# hunger_cube.net
KiCad netlist of a schematic drawn in EAGLE
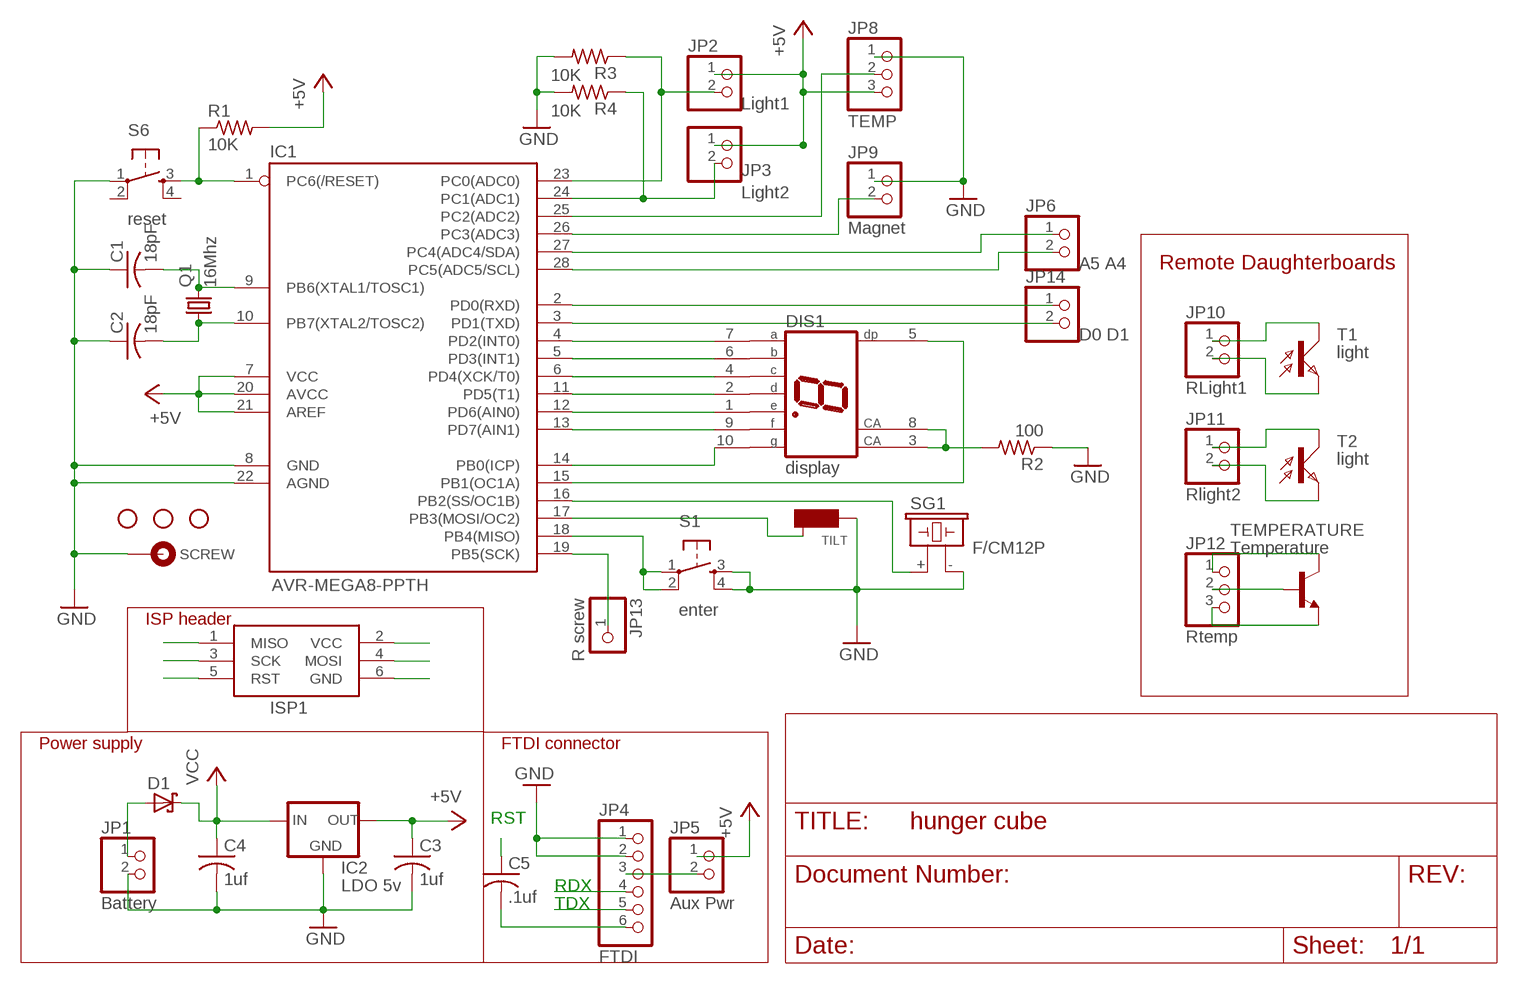
[diagram p0: schematic, sheet 1]

(export (version "E")
  (design (tool "Eeschema 10.0.6"))
  (components
    (comp (ref "C1")
      (value "18pF")
      (footprint "eagle-import:C025-050X050")
      (libsource (lib "eagle-import") (part "C-US025-050X050"))
    )
    (comp (ref "C2")
      (value "18pF")
      (footprint "eagle-import:C025-050X050")
      (libsource (lib "eagle-import") (part "C-US025-050X050"))
    )
    (comp (ref "C3")
      (value "1uf")
      (footprint "eagle-import:C025-050X050")
      (libsource (lib "eagle-import") (part "C-US025-050X050"))
    )
    (comp (ref "C4")
      (value "1uf")
      (footprint "eagle-import:C025-050X050")
      (libsource (lib "eagle-import") (part "C-US025-050X050"))
    )
    (comp (ref "C5")
      (value ".1uf")
      (footprint "eagle-import:C025-050X050")
      (libsource (lib "eagle-import") (part "C-US025-050X050"))
    )
    (comp (ref "D1")
      (value "SCHOTTKY-DIODEDO41")
      (footprint "eagle-import:DO41-10")
      (libsource (lib "eagle-import") (part "SCHOTTKY-DIODEDO41"))
    )
    (comp (ref "DIS1")
      (value "display")
      (footprint "eagle-import:HDSP-M")
      (libsource (lib "eagle-import") (part "HD-H101"))
    )
    (comp (ref "IC1")
      (value "AVR-MEGA8-PPTH")
      (footprint "eagle-import:DIL28-3")
      (libsource (lib "eagle-import") (part "AVR-MEGA8-PPTH"))
    )
    (comp (ref "IC2")
      (value "LDO 5v")
      (footprint "eagle-import:TO92-INLINE")
      (libsource (lib "eagle-import") (part "MCP1700INLINE"))
    )
    (comp (ref "ISP1")
      (value "AVRISP-6")
      (footprint "eagle-import:AVRISP")
      (libsource (lib "eagle-import") (part "AVRISP-6"))
    )
    (comp (ref "JP1")
      (value "Battery")
      (footprint "eagle-import:1X02")
      (libsource (lib "eagle-import") (part "PINHD-1X2"))
    )
    (comp (ref "JP2")
      (value "Light1")
      (footprint "eagle-import:1X02")
      (libsource (lib "eagle-import") (part "PINHD-1X2"))
    )
    (comp (ref "JP3")
      (value "Light2")
      (footprint "eagle-import:1X02")
      (libsource (lib "eagle-import") (part "PINHD-1X2"))
    )
    (comp (ref "JP4")
      (value "FTDI")
      (footprint "eagle-import:1X06")
      (libsource (lib "eagle-import") (part "PINHD-1X6"))
    )
    (comp (ref "JP5")
      (value "Aux Pwr")
      (footprint "eagle-import:1X02")
      (libsource (lib "eagle-import") (part "PINHD-1X2"))
    )
    (comp (ref "JP6")
      (value "A5 A4")
      (footprint "eagle-import:1X02")
      (libsource (lib "eagle-import") (part "PINHD-1X2"))
    )
    (comp (ref "JP7")
      (value "Connected screw hole")
      (footprint "eagle-import:SCREW-HOLE-PAD")
      (libsource (lib "eagle-import") (part "CONNECTED-SCREW-HOLE"))
    )
    (comp (ref "JP8")
      (value "TEMP")
      (footprint "eagle-import:1X03")
      (libsource (lib "eagle-import") (part "PINHD-1X3"))
    )
    (comp (ref "JP9")
      (value "Magnet")
      (footprint "eagle-import:1X02")
      (libsource (lib "eagle-import") (part "PINHD-1X2"))
    )
    (comp (ref "JP10")
      (value "RLight1")
      (footprint "eagle-import:1X02")
      (libsource (lib "eagle-import") (part "PINHD-1X2"))
    )
    (comp (ref "JP11")
      (value "Rlight2")
      (footprint "eagle-import:1X02")
      (libsource (lib "eagle-import") (part "PINHD-1X2"))
    )
    (comp (ref "JP12")
      (value "Rtemp")
      (footprint "eagle-import:1X03")
      (libsource (lib "eagle-import") (part "PINHD-1X3"))
    )
    (comp (ref "JP13")
      (value "R screw")
      (footprint "eagle-import:1X01")
      (libsource (lib "eagle-import") (part "PINHD-1X1"))
    )
    (comp (ref "JP14")
      (value "D0 D1")
      (footprint "eagle-import:1X02")
      (libsource (lib "eagle-import") (part "PINHD-1X2"))
    )
    (comp (ref "Q1")
      (value "16Mhz")
      (footprint "eagle-import:HC49US")
      (libsource (lib "eagle-import") (part "CRYSTALHC49US"))
    )
    (comp (ref "R1")
      (value "10K")
      (footprint "eagle-import:0207_12")
      (libsource (lib "eagle-import") (part "R-US_0207/12"))
    )
    (comp (ref "R2")
      (value "100")
      (footprint "eagle-import:0207_12")
      (libsource (lib "eagle-import") (part "R-US_0207/12"))
    )
    (comp (ref "R3")
      (value "10K")
      (footprint "eagle-import:0207_12")
      (libsource (lib "eagle-import") (part "R-US_0207/12"))
    )
    (comp (ref "R4")
      (value "10K")
      (footprint "eagle-import:0207_12")
      (libsource (lib "eagle-import") (part "R-US_0207/12"))
    )
    (comp (ref "S1")
      (value "enter")
      (footprint "eagle-import:TACTILE-PTH")
      (libsource (lib "eagle-import") (part "TAC_SWITCHPTH"))
    )
    (comp (ref "S6")
      (value "reset")
      (footprint "eagle-import:TACTILE-PTH")
      (libsource (lib "eagle-import") (part "TAC_SWITCHPTH"))
    )
    (comp (ref "SG1")
      (value "F/CM12P")
      (footprint "eagle-import:F_CM12P")
      (libsource (lib "eagle-import") (part "F/CM12P"))
    )
    (comp (ref "ST1")
      (value "STAND-OFF")
      (footprint "eagle-import:STAND-OFF")
      (libsource (lib "eagle-import") (part "STAND-OFF"))
    )
    (comp (ref "ST2")
      (value "STAND-OFF")
      (footprint "eagle-import:STAND-OFF")
      (libsource (lib "eagle-import") (part "STAND-OFF"))
    )
    (comp (ref "ST3")
      (value "STAND-OFF")
      (footprint "eagle-import:STAND-OFF")
      (libsource (lib "eagle-import") (part "STAND-OFF"))
    )
    (comp (ref "T1")
      (value "light")
      (footprint "eagle-import:BPX81")
      (libsource (lib "eagle-import") (part "BPX81"))
    )
    (comp (ref "T2")
      (value "light")
      (footprint "eagle-import:BPX81")
      (libsource (lib "eagle-import") (part "BPX81"))
    )
    (comp (ref "TEMPERATURE")
      (value "Temperature")
      (footprint "eagle-import:TO92-EBC")
      (libsource (lib "eagle-import") (part "-NPN-TO92-EBC"))
    )
    (comp (ref "TILT")
      (value "TILT-SENSOR")
      (footprint "eagle-import:TILT")
      (libsource (lib "eagle-import") (part "TILT-SENSOR"))
    )
  )
  (nets
    (net (code "1") (name "+5V") (class "Default")
      (node (ref "C3") (pin "1") (pinfunction "1_1") (pintype "passive"))
      (node (ref "IC1") (pin "20") (pinfunction "AVCC_20") (pintype "bidirectional"))
      (node (ref "IC1") (pin "21") (pinfunction "AREF_21") (pintype "bidirectional"))
      (node (ref "IC1") (pin "7") (pinfunction "VCC_7") (pintype "bidirectional"))
      (node (ref "IC2") (pin "3") (pinfunction "OUT_3") (pintype "passive"))
      (node (ref "ISP1") (pin "2") (pinfunction "VCC_2") (pintype "power_in"))
      (node (ref "JP2") (pin "1") (pinfunction "1_1") (pintype "passive"))
      (node (ref "JP3") (pin "1") (pinfunction "1_1") (pintype "passive"))
      (node (ref "JP5") (pin "1") (pinfunction "1_1") (pintype "passive"))
      (node (ref "JP8") (pin "3") (pinfunction "3_3") (pintype "passive"))
      (node (ref "R1") (pin "2") (pinfunction "2_2") (pintype "passive"))
    )
    (net (code "2") (name "/D0-RDX") (class "Default")
      (node (ref "IC1") (pin "2") (pinfunction "PD0(RXD)_2") (pintype "bidirectional"))
      (node (ref "JP14") (pin "1") (pinfunction "1_1") (pintype "passive"))
      (node (ref "JP4") (pin "4") (pinfunction "4_4") (pintype "passive"))
    )
    (net (code "3") (name "/D1-TDX") (class "Default")
      (node (ref "IC1") (pin "3") (pinfunction "PD1(TXD)_3") (pintype "bidirectional"))
      (node (ref "JP14") (pin "2") (pinfunction "2_2") (pintype "passive"))
      (node (ref "JP4") (pin "5") (pinfunction "5_5") (pintype "passive"))
    )
    (net (code "4") (name "/D11-MOSI-TILT") (class "Default")
      (node (ref "IC1") (pin "17") (pinfunction "PB3(MOSI/OC2)_17") (pintype "bidirectional"))
      (node (ref "ISP1") (pin "4") (pinfunction "MOSI_4") (pintype "output"))
      (node (ref "TILT") (pin "SLEEVE") (pinfunction "SLEEVE_SLEEVE") (pintype "bidirectional"))
    )
    (net (code "5") (name "/D12-MISO-ENTER") (class "Default")
      (node (ref "IC1") (pin "18") (pinfunction "PB4(MISO)_18") (pintype "bidirectional"))
      (node (ref "ISP1") (pin "1") (pinfunction "MISO_1") (pintype "input"))
      (node (ref "S1") (pin "1") (pinfunction "1_1") (pintype "passive"))
      (node (ref "S1") (pin "2") (pinfunction "2_2") (pintype "passive"))
    )
    (net (code "6") (name "/D13-SCK-SCREW") (class "Default")
      (node (ref "IC1") (pin "19") (pinfunction "PB5(SCK)_19") (pintype "bidirectional"))
      (node (ref "ISP1") (pin "3") (pinfunction "SCK_3") (pintype "output"))
      (node (ref "JP13") (pin "1") (pinfunction "1_1") (pintype "passive"))
    )
    (net (code "7") (name "/RST") (class "Default")
      (node (ref "C5") (pin "1") (pinfunction "1_1") (pintype "passive"))
      (node (ref "IC1") (pin "1") (pinfunction "PC6(/RESET)_1") (pintype "bidirectional"))
      (node (ref "ISP1") (pin "5") (pinfunction "RST_5") (pintype "output"))
      (node (ref "R1") (pin "1") (pinfunction "1_1") (pintype "passive"))
      (node (ref "S6") (pin "3") (pinfunction "3_3") (pintype "passive"))
    )
    (net (code "8") (name "GND") (class "Default")
      (node (ref "C1") (pin "1") (pinfunction "1_1") (pintype "passive"))
      (node (ref "C2") (pin "1") (pinfunction "1_1") (pintype "passive"))
      (node (ref "C3") (pin "2") (pinfunction "2_2") (pintype "passive"))
      (node (ref "C4") (pin "2") (pinfunction "2_2") (pintype "passive"))
      (node (ref "IC1") (pin "22") (pinfunction "AGND_22") (pintype "bidirectional"))
      (node (ref "IC1") (pin "8") (pinfunction "GND_8") (pintype "bidirectional"))
      (node (ref "IC2") (pin "1") (pinfunction "GND_1") (pintype "input"))
      (node (ref "ISP1") (pin "6") (pinfunction "GND_6") (pintype "power_in"))
      (node (ref "JP1") (pin "2") (pinfunction "2_2") (pintype "passive"))
      (node (ref "JP4") (pin "1") (pinfunction "1_1") (pintype "passive"))
      (node (ref "JP4") (pin "2") (pinfunction "2_2") (pintype "passive"))
      (node (ref "JP7") (pin "SCREW") (pinfunction "SCREW_SCREW") (pintype "bidirectional"))
      (node (ref "JP8") (pin "1") (pinfunction "1_1") (pintype "passive"))
      (node (ref "JP9") (pin "1") (pinfunction "1_1") (pintype "passive"))
      (node (ref "R2") (pin "1") (pinfunction "1_1") (pintype "passive"))
      (node (ref "R3") (pin "2") (pinfunction "2_2") (pintype "passive"))
      (node (ref "R4") (pin "2") (pinfunction "2_2") (pintype "passive"))
      (node (ref "S1") (pin "3") (pinfunction "3_3") (pintype "passive"))
      (node (ref "S1") (pin "4") (pinfunction "4_4") (pintype "passive"))
      (node (ref "S6") (pin "1") (pinfunction "1_1") (pintype "passive"))
      (node (ref "SG1") (pin "-") (pinfunction "2_-") (pintype "passive"))
      (node (ref "TILT") (pin "CENTER") (pinfunction "CENTER_CENTER") (pintype "bidirectional"))
    )
    (net (code "9") (name "Net-(C5-Pad2)") (class "Default")
      (node (ref "C5") (pin "2") (pinfunction "2_2") (pintype "passive"))
      (node (ref "JP4") (pin "6") (pinfunction "6_6") (pintype "passive"))
    )
    (net (code "10") (name "Net-(D1-PadA)") (class "Default")
      (node (ref "D1") (pin "A") (pinfunction "A_A") (pintype "passive"))
      (node (ref "JP1") (pin "1") (pinfunction "1_1") (pintype "passive"))
    )
    (net (code "11") (name "Net-(DIS1-A)") (class "Default")
      (node (ref "DIS1") (pin "7") (pinfunction "A_7") (pintype "passive"))
      (node (ref "IC1") (pin "4") (pinfunction "PD2(INT0)_4") (pintype "bidirectional"))
    )
    (net (code "12") (name "Net-(DIS1-B)") (class "Default")
      (node (ref "DIS1") (pin "6") (pinfunction "B_6") (pintype "passive"))
      (node (ref "IC1") (pin "5") (pinfunction "PD3(INT1)_5") (pintype "bidirectional"))
    )
    (net (code "13") (name "Net-(DIS1-C)") (class "Default")
      (node (ref "DIS1") (pin "4") (pinfunction "C_4") (pintype "passive"))
      (node (ref "IC1") (pin "6") (pinfunction "PD4(XCK/T0)_6") (pintype "bidirectional"))
    )
    (net (code "14") (name "Net-(DIS1-CA-Pad3)") (class "Default")
      (node (ref "DIS1") (pin "3") (pinfunction "CA_3") (pintype "passive"))
      (node (ref "DIS1") (pin "8") (pinfunction "CA_8") (pintype "passive"))
      (node (ref "R2") (pin "2") (pinfunction "2_2") (pintype "passive"))
    )
    (net (code "15") (name "Net-(DIS1-D)") (class "Default")
      (node (ref "DIS1") (pin "2") (pinfunction "D_2") (pintype "passive"))
      (node (ref "IC1") (pin "11") (pinfunction "PD5(T1)_11") (pintype "bidirectional"))
    )
    (net (code "16") (name "Net-(DIS1-DP)") (class "Default")
      (node (ref "DIS1") (pin "5") (pinfunction "DP_5") (pintype "passive"))
      (node (ref "IC1") (pin "15") (pinfunction "PB1(OC1A)_15") (pintype "bidirectional"))
    )
    (net (code "17") (name "Net-(DIS1-E)") (class "Default")
      (node (ref "DIS1") (pin "1") (pinfunction "E_1") (pintype "passive"))
      (node (ref "IC1") (pin "12") (pinfunction "PD6(AIN0)_12") (pintype "bidirectional"))
    )
    (net (code "18") (name "Net-(DIS1-F)") (class "Default")
      (node (ref "DIS1") (pin "9") (pinfunction "F_9") (pintype "passive"))
      (node (ref "IC1") (pin "13") (pinfunction "PD7(AIN1)_13") (pintype "bidirectional"))
    )
    (net (code "19") (name "Net-(DIS1-G)") (class "Default")
      (node (ref "DIS1") (pin "10") (pinfunction "G_10") (pintype "passive"))
      (node (ref "IC1") (pin "14") (pinfunction "PB0(ICP)_14") (pintype "bidirectional"))
    )
    (net (code "20") (name "Net-(IC1-PB2(SS{slash}OC1B))") (class "Default")
      (node (ref "IC1") (pin "16") (pinfunction "PB2(SS/OC1B)_16") (pintype "bidirectional"))
      (node (ref "SG1") (pin "+") (pinfunction "1_+") (pintype "passive"))
    )
    (net (code "21") (name "Net-(IC1-PB6(XTAL1{slash}TOSC1))") (class "Default")
      (node (ref "C1") (pin "2") (pinfunction "2_2") (pintype "passive"))
      (node (ref "IC1") (pin "9") (pinfunction "PB6(XTAL1/TOSC1)_9") (pintype "bidirectional"))
      (node (ref "Q1") (pin "2") (pinfunction "2_2") (pintype "passive"))
    )
    (net (code "22") (name "Net-(IC1-PB7(XTAL2{slash}TOSC2))") (class "Default")
      (node (ref "C2") (pin "2") (pinfunction "2_2") (pintype "passive"))
      (node (ref "IC1") (pin "10") (pinfunction "PB7(XTAL2/TOSC2)_10") (pintype "bidirectional"))
      (node (ref "Q1") (pin "1") (pinfunction "1_1") (pintype "passive"))
    )
    (net (code "23") (name "Net-(IC1-PC0(ADC0))") (class "Default")
      (node (ref "IC1") (pin "23") (pinfunction "PC0(ADC0)_23") (pintype "bidirectional"))
      (node (ref "JP2") (pin "2") (pinfunction "2_2") (pintype "passive"))
      (node (ref "R3") (pin "1") (pinfunction "1_1") (pintype "passive"))
    )
    (net (code "24") (name "Net-(IC1-PC1(ADC1))") (class "Default")
      (node (ref "IC1") (pin "24") (pinfunction "PC1(ADC1)_24") (pintype "bidirectional"))
      (node (ref "JP3") (pin "2") (pinfunction "2_2") (pintype "passive"))
      (node (ref "R4") (pin "1") (pinfunction "1_1") (pintype "passive"))
    )
    (net (code "25") (name "Net-(IC1-PC2(ADC2))") (class "Default")
      (node (ref "IC1") (pin "25") (pinfunction "PC2(ADC2)_25") (pintype "bidirectional"))
      (node (ref "JP8") (pin "2") (pinfunction "2_2") (pintype "passive"))
    )
    (net (code "26") (name "Net-(IC1-PC3(ADC3))") (class "Default")
      (node (ref "IC1") (pin "26") (pinfunction "PC3(ADC3)_26") (pintype "bidirectional"))
      (node (ref "JP9") (pin "2") (pinfunction "2_2") (pintype "passive"))
    )
    (net (code "27") (name "Net-(IC1-PC4(ADC4{slash}SDA))") (class "Default")
      (node (ref "IC1") (pin "27") (pinfunction "PC4(ADC4/SDA)_27") (pintype "bidirectional"))
      (node (ref "JP6") (pin "1") (pinfunction "1_1") (pintype "passive"))
    )
    (net (code "28") (name "Net-(IC1-PC5(ADC5{slash}SCL))") (class "Default")
      (node (ref "IC1") (pin "28") (pinfunction "PC5(ADC5/SCL)_28") (pintype "bidirectional"))
      (node (ref "JP6") (pin "2") (pinfunction "2_2") (pintype "passive"))
    )
    (net (code "29") (name "Net-(JP4-Pad3)") (class "Default")
      (node (ref "JP4") (pin "3") (pinfunction "3_3") (pintype "passive"))
      (node (ref "JP5") (pin "2") (pinfunction "2_2") (pintype "passive"))
    )
    (net (code "30") (name "Net-(JP10-Pad1)") (class "Default")
      (node (ref "JP10") (pin "1") (pinfunction "1_1") (pintype "passive"))
      (node (ref "T1") (pin "C") (pinfunction "C_C") (pintype "passive"))
    )
    (net (code "31") (name "Net-(JP10-Pad2)") (class "Default")
      (node (ref "JP10") (pin "2") (pinfunction "2_2") (pintype "passive"))
      (node (ref "T1") (pin "E") (pinfunction "E_E") (pintype "passive"))
    )
    (net (code "32") (name "Net-(JP11-Pad1)") (class "Default")
      (node (ref "JP11") (pin "1") (pinfunction "1_1") (pintype "passive"))
      (node (ref "T2") (pin "C") (pinfunction "C_C") (pintype "passive"))
    )
    (net (code "33") (name "Net-(JP11-Pad2)") (class "Default")
      (node (ref "JP11") (pin "2") (pinfunction "2_2") (pintype "passive"))
      (node (ref "T2") (pin "E") (pinfunction "E_E") (pintype "passive"))
    )
    (net (code "34") (name "Net-(JP12-Pad1)") (class "Default")
      (node (ref "JP12") (pin "1") (pinfunction "1_1") (pintype "passive"))
      (node (ref "TEMPERATURE") (pin "C") (pinfunction "C_C") (pintype "passive"))
    )
    (net (code "35") (name "Net-(JP12-Pad2)") (class "Default")
      (node (ref "JP12") (pin "2") (pinfunction "2_2") (pintype "passive"))
      (node (ref "TEMPERATURE") (pin "B") (pinfunction "B_B") (pintype "passive"))
    )
    (net (code "36") (name "Net-(JP12-Pad3)") (class "Default")
      (node (ref "JP12") (pin "3") (pinfunction "3_3") (pintype "passive"))
      (node (ref "TEMPERATURE") (pin "E") (pinfunction "E_E") (pintype "passive"))
    )
    (net (code "37") (name "VCC") (class "Default")
      (node (ref "C4") (pin "1") (pinfunction "1_1") (pintype "passive"))
      (node (ref "D1") (pin "C") (pinfunction "C_C") (pintype "passive"))
      (node (ref "IC2") (pin "2") (pinfunction "IN_2") (pintype "input"))
    )
    (net (code "38") (name "unconnected-(S6-Pad2)") (class "Default")
      (node (ref "S6") (pin "2") (pinfunction "2_2") (pintype "passive"))
    )
    (net (code "39") (name "unconnected-(S6-Pad4)") (class "Default")
      (node (ref "S6") (pin "4") (pinfunction "4_4") (pintype "passive"))
    )
  )
)
